# SCH_OnBoard-Business-Card_2024-06-20.net
KiCad netlist of a schematic drawn in EasyEDA
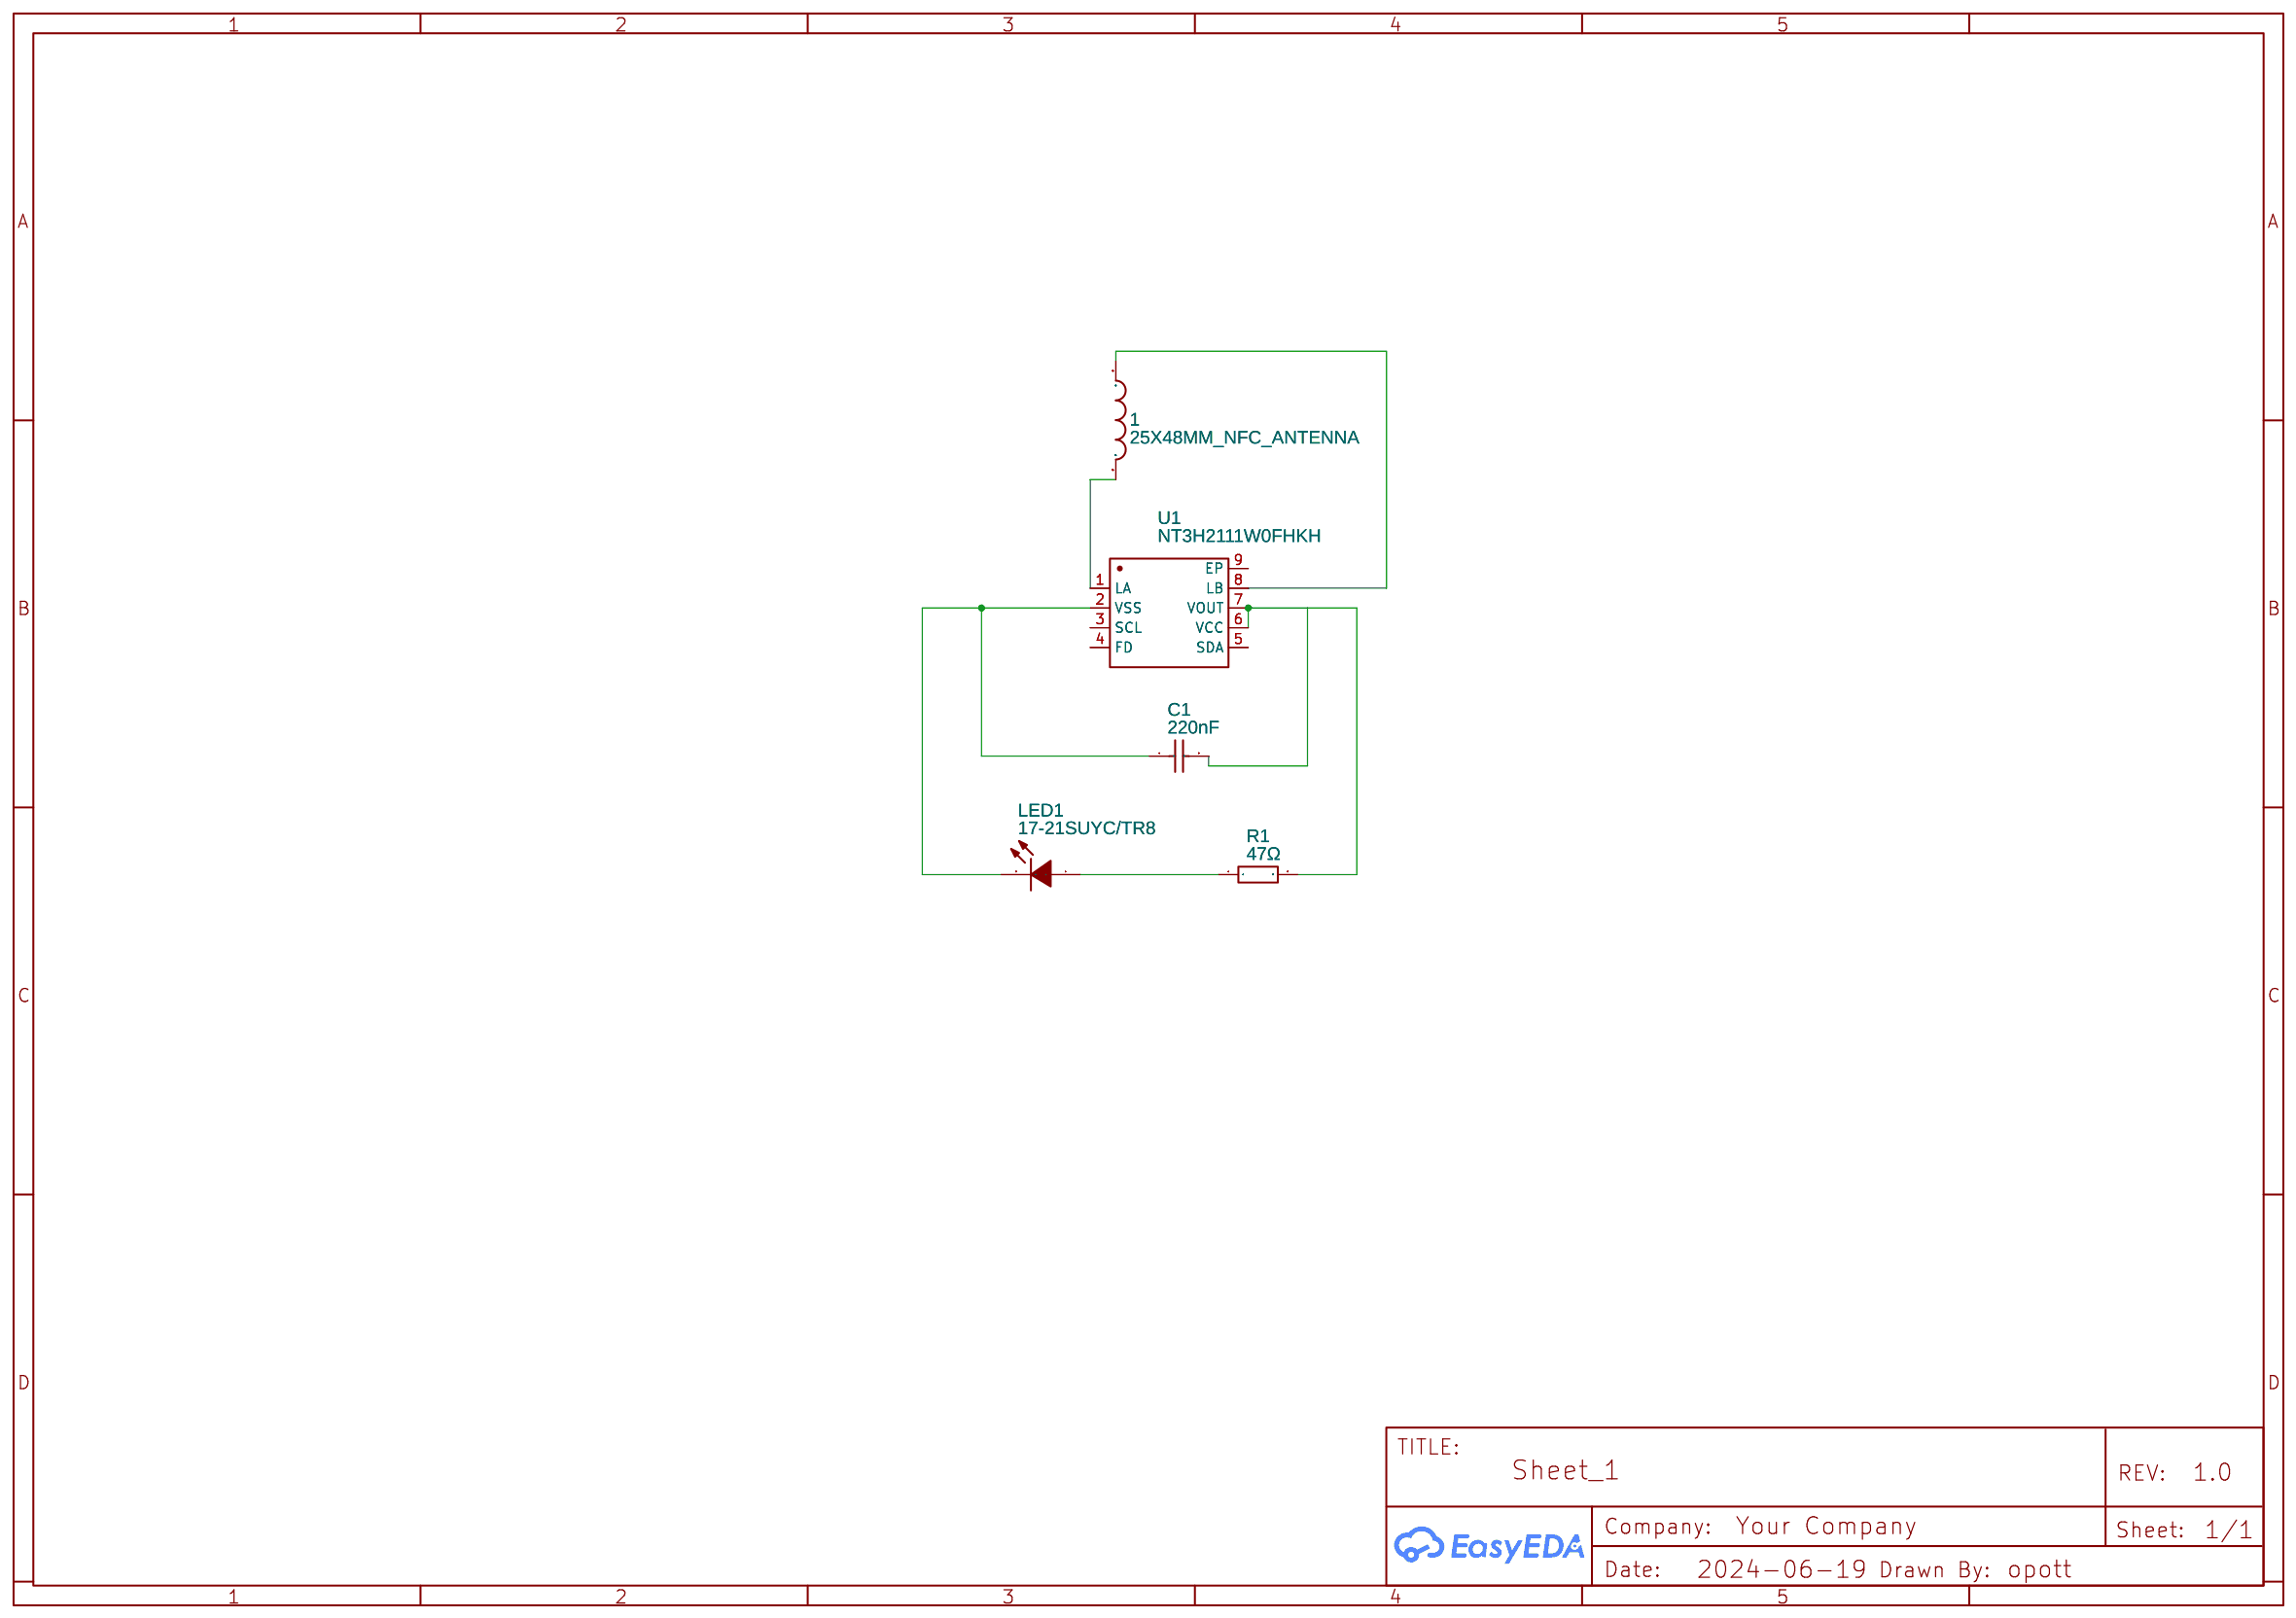
[diagram p0: schematic sheet]

(export (version "E")
  (design (tool "Eeschema 10.0.6"))
  (components
    (comp (ref "1") (value "25X48MM_NFC_ANTENNA") (libsource (lib "") (part "25X48MM_NFC_ANTENNA")))
    (comp (ref "C1")
      (value "220nF")
      (fields
        (field (name "Manufacturer Part") "CL10B224KA8NNNC")
        (field (name "Manufacturer") "SAMSUNG(三星)")
      )
      (libsource (lib "") (part "CL10B224KA8NNNC"))
    )
    (comp (ref "LED1")
      (value "17-21SUYC/TR8")
      (fields (field (name "Manufacturer Part") "KT-0805黄灯") (field (name "Manufacturer") "KENTO"))
      (libsource (lib "") (part "17-21SUYC/TR8"))
    )
    (comp (ref "R1")
      (value "47Ω")
      (fields
        (field (name "Manufacturer Part") "0603WAF470JT5E")
        (field (name "Manufacturer") "UNI-ROYAL(厚声)")
      )
      (libsource (lib "") (part "0603WAF470JT5E"))
    )
    (comp (ref "U1")
      (value "NT3H2111W0FHKH")
      (fields (field (name "Manufacturer") "NXP(恩智浦)"))
      (libsource (lib "") (part "NT3H2111W0FHKH"))
    )
  )
  (nets
    (net (code "1") (name "Net-(LED1-+)") (class "Default")
      (node (ref "LED1") (pin "1") (pinfunction "+_1") (pintype "unspecified"))
      (node (ref "R1") (pin "1") (pinfunction "1_1") (pintype "input"))
    )
    (net (code "2") (name "Net-(LED1--)") (class "Default")
      (node (ref "C1") (pin "1") (pinfunction "1_1") (pintype "input"))
      (node (ref "LED1") (pin "2") (pinfunction "-_2") (pintype "unspecified"))
      (node (ref "U1") (pin "2") (pinfunction "VSS_2") (pintype "unspecified"))
    )
    (net (code "3") (name "Net-(U1-LA)") (class "Default")
      (node (ref "1") (pin "P$2") (pinfunction "P$2_P$2") (pintype "bidirectional"))
      (node (ref "U1") (pin "1") (pinfunction "LA_1") (pintype "unspecified"))
    )
    (net (code "4") (name "Net-(U1-LB)") (class "Default")
      (node (ref "1") (pin "P$1") (pinfunction "P$1_P$1") (pintype "bidirectional"))
      (node (ref "U1") (pin "8") (pinfunction "LB_8") (pintype "unspecified"))
    )
    (net (code "5") (name "Net-(U1-VCC)") (class "Default")
      (node (ref "C1") (pin "2") (pinfunction "2_2") (pintype "input"))
      (node (ref "R1") (pin "2") (pinfunction "2_2") (pintype "input"))
      (node (ref "U1") (pin "6") (pinfunction "VCC_6") (pintype "unspecified"))
      (node (ref "U1") (pin "7") (pinfunction "VOUT_7") (pintype "unspecified"))
    )
    (net (code "6") (name "unconnected-(U1-EP-Pad9)") (class "Default")
      (node (ref "U1") (pin "9") (pinfunction "EP_9") (pintype "unspecified"))
    )
    (net (code "7") (name "unconnected-(U1-FD-Pad4)") (class "Default")
      (node (ref "U1") (pin "4") (pinfunction "FD_4") (pintype "unspecified"))
    )
    (net (code "8") (name "unconnected-(U1-SCL-Pad3)") (class "Default")
      (node (ref "U1") (pin "3") (pinfunction "SCL_3") (pintype "unspecified"))
    )
    (net (code "9") (name "unconnected-(U1-SDA-Pad5)") (class "Default")
      (node (ref "U1") (pin "5") (pinfunction "SDA_5") (pintype "unspecified"))
    )
  )
)
